# power.net
KiCad netlist of a schematic drawn in Altium Designer
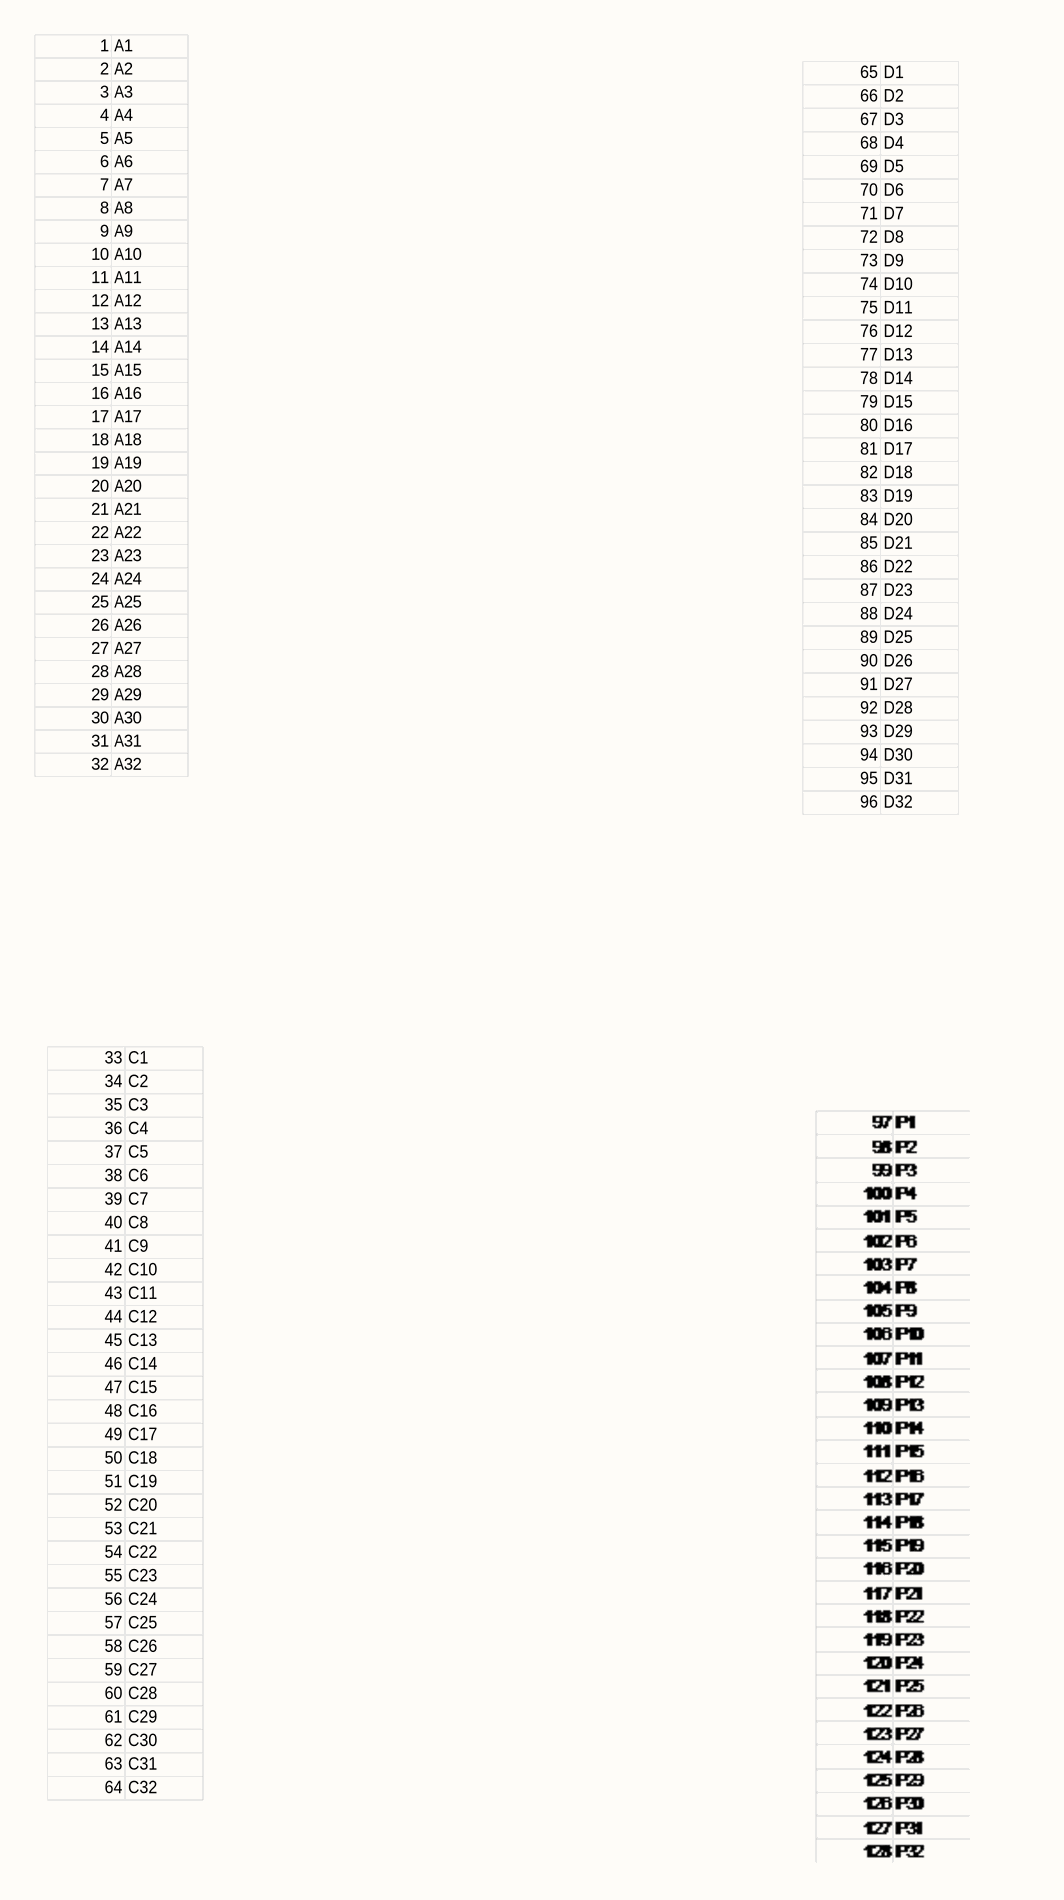
[diagram p0: power.SchDoc, left]
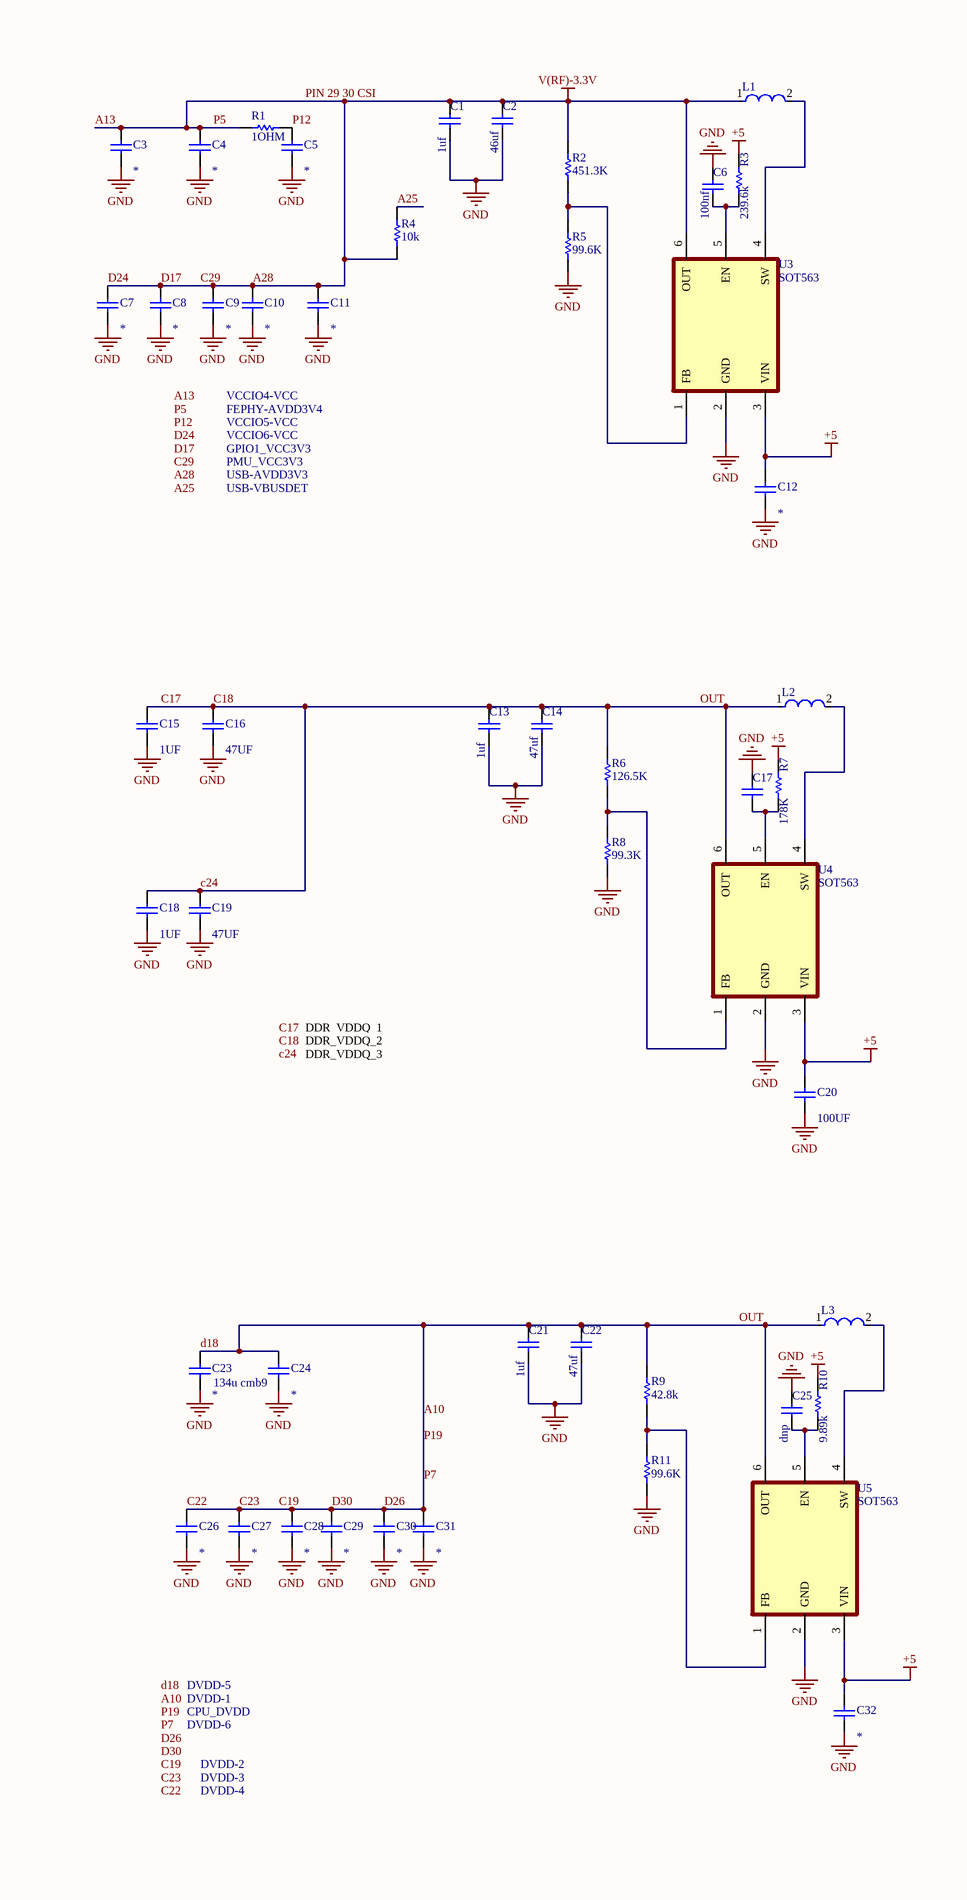
[diagram p1: power.SchDoc, right]

(export (version "E")
  (design (tool "Eeschema 10.0.6"))
  (components
    (comp (ref "C1")
      (value "1uf")
      (footprint "CAPC1005X56X25LL10T15")
      (libsource (lib "Altium Content Vault") (part "CAP"))
    )
    (comp (ref "C2")
      (value "46uf")
      (footprint "CAPC1005X56X25LL10T15")
      (libsource (lib "Altium Content Vault") (part "CAP"))
    )
    (comp (ref "C3")
      (value "*")
      (footprint "CAPC1005X56X25LL10T15")
      (libsource (lib "Altium Content Vault") (part "CAP"))
    )
    (comp (ref "C4")
      (value "*")
      (footprint "CAPC1005X56X25LL10T15")
      (libsource (lib "Altium Content Vault") (part "CAP"))
    )
    (comp (ref "C5")
      (value "*")
      (footprint "CAPC1005X56X25LL10T15")
      (libsource (lib "Altium Content Vault") (part "CAP"))
    )
    (comp (ref "C6")
      (value "100nf")
      (footprint "CAPC1005X56X25LL10T15")
      (libsource (lib "Altium Content Vault") (part "CAP"))
    )
    (comp (ref "C7")
      (value "*")
      (footprint "CAPC1005X56X25LL10T15")
      (libsource (lib "Altium Content Vault") (part "CAP"))
    )
    (comp (ref "C8")
      (value "*")
      (footprint "CAPC1005X56X25LL10T15")
      (libsource (lib "Altium Content Vault") (part "CAP"))
    )
    (comp (ref "C9")
      (value "*")
      (footprint "CAPC1005X56X25LL10T15")
      (libsource (lib "Altium Content Vault") (part "CAP"))
    )
    (comp (ref "C10")
      (value "*")
      (footprint "CAPC1005X56X25LL10T15")
      (libsource (lib "Altium Content Vault") (part "CAP"))
    )
    (comp (ref "C11")
      (value "*")
      (footprint "CAPC1005X56X25LL10T15")
      (libsource (lib "Altium Content Vault") (part "CAP"))
    )
    (comp (ref "C12")
      (value "*")
      (footprint "CAPC1005X56X25LL10T15")
      (libsource (lib "Altium Content Vault") (part "CAP"))
    )
    (comp (ref "C13")
      (value "1uf")
      (footprint "CAPC1005X56X25LL10T15")
      (libsource (lib "Altium Content Vault") (part "CAP"))
    )
    (comp (ref "C14")
      (value "47uf")
      (footprint "CAPC1005X56X25LL10T15")
      (libsource (lib "Altium Content Vault") (part "CAP"))
    )
    (comp (ref "C15")
      (value "1UF")
      (footprint "CAPC1005X56X25LL10T15")
      (libsource (lib "Altium Content Vault") (part "CAP"))
    )
    (comp (ref "C16")
      (value "47UF")
      (footprint "CAPC1005X56X25LL10T15")
      (libsource (lib "Altium Content Vault") (part "CAP"))
    )
    (comp (ref "C17")
      (value "~")
      (footprint "CAPC1005X56X25LL10T15")
      (libsource (lib "Altium Content Vault") (part "CAP"))
    )
    (comp (ref "C18")
      (value "1UF")
      (footprint "CAPC1005X56X25LL10T15")
      (libsource (lib "Altium Content Vault") (part "CAP"))
    )
    (comp (ref "C19")
      (value "47UF")
      (footprint "CAPC1005X56X25LL10T15")
      (libsource (lib "Altium Content Vault") (part "CAP"))
    )
    (comp (ref "C20")
      (value "100UF")
      (footprint "CAPC1005X56X25LL10T15")
      (libsource (lib "Altium Content Vault") (part "CAP"))
    )
    (comp (ref "C21")
      (value "1uf")
      (footprint "CAPC1005X56X25LL10T15")
      (libsource (lib "Altium Content Vault") (part "CAP"))
    )
    (comp (ref "C22")
      (value "47uf")
      (footprint "CAPC1005X56X25LL10T15")
      (libsource (lib "Altium Content Vault") (part "CAP"))
    )
    (comp (ref "C23")
      (value "*")
      (footprint "CAPC1005X56X25LL10T15")
      (libsource (lib "Altium Content Vault") (part "CAP"))
    )
    (comp (ref "C24")
      (value "*")
      (footprint "CAPC1005X56X25LL10T15")
      (libsource (lib "Altium Content Vault") (part "CAP"))
    )
    (comp (ref "C25")
      (value "dnp")
      (footprint "CAPC1005X56X25LL10T15")
      (libsource (lib "Altium Content Vault") (part "CAP"))
    )
    (comp (ref "C26")
      (value "*")
      (footprint "CAPC1005X56X25LL10T15")
      (libsource (lib "Altium Content Vault") (part "CAP"))
    )
    (comp (ref "C27")
      (value "*")
      (footprint "CAPC1005X56X25LL10T15")
      (libsource (lib "Altium Content Vault") (part "CAP"))
    )
    (comp (ref "C28")
      (value "*")
      (footprint "CAPC1005X56X25LL10T15")
      (libsource (lib "Altium Content Vault") (part "CAP"))
    )
    (comp (ref "C29")
      (value "*")
      (footprint "CAPC1005X56X25LL10T15")
      (libsource (lib "Altium Content Vault") (part "CAP"))
    )
    (comp (ref "C30")
      (value "*")
      (footprint "CAPC1005X56X25LL10T15")
      (libsource (lib "Altium Content Vault") (part "CAP"))
    )
    (comp (ref "C31")
      (value "*")
      (footprint "CAPC1005X56X25LL10T15")
      (libsource (lib "Altium Content Vault") (part "CAP"))
    )
    (comp (ref "C32")
      (value "*")
      (footprint "CAPC1005X56X25LL10T15")
      (libsource (lib "Altium Content Vault") (part "CAP"))
    )
    (comp (ref "L1")
      (value "~")
      (footprint "FP-LQH31CN_03-MFG")
      (libsource (lib "Altium Content Vault") (part "725321dda6339637d4d059423bc1c3c"))
    )
    (comp (ref "L2")
      (value "~")
      (footprint "FP-LQH31CN_03-MFG")
      (libsource (lib "Altium Content Vault") (part "725321dda6339637d4d059423bc1c3c"))
    )
    (comp (ref "L3")
      (value "~")
      (footprint "FP-LQH31CN_03-MFG")
      (libsource (lib "Altium Content Vault") (part "725321dda6339637d4d059423bc1c3c"))
    )
    (comp (ref "R1")
      (value "1OHM")
      (footprint "RESC1005X40X25LL05T10")
      (libsource (lib "Altium Content Vault") (part "RES"))
    )
    (comp (ref "R2")
      (value "451.3K")
      (footprint "RESC1005X40X25LL05T10")
      (libsource (lib "Altium Content Vault") (part "RES"))
    )
    (comp (ref "R3")
      (value "239.6k")
      (footprint "RESC1005X40X25LL05T10")
      (libsource (lib "Altium Content Vault") (part "RES"))
    )
    (comp (ref "R4")
      (value "10k")
      (footprint "RESC1005X40X25LL05T10")
      (libsource (lib "Altium Content Vault") (part "RES"))
    )
    (comp (ref "R5")
      (value "99.6K")
      (footprint "RESC1005X40X25LL05T10")
      (libsource (lib "Altium Content Vault") (part "RES"))
    )
    (comp (ref "R6")
      (value "126.5K")
      (footprint "RESC1005X40X25LL05T10")
      (libsource (lib "Altium Content Vault") (part "RES"))
    )
    (comp (ref "R7")
      (value "178K")
      (footprint "RESC1005X40X25LL05T10")
      (libsource (lib "Altium Content Vault") (part "RES"))
    )
    (comp (ref "R8")
      (value "99.3K")
      (footprint "RESC1005X40X25LL05T10")
      (libsource (lib "Altium Content Vault") (part "RES"))
    )
    (comp (ref "R9")
      (value "42.8k")
      (footprint "RESC1005X40X25LL05T10")
      (libsource (lib "Altium Content Vault") (part "RES"))
    )
    (comp (ref "R10")
      (value "9.89k")
      (footprint "RESC1005X40X25LL05T10")
      (libsource (lib "Altium Content Vault") (part "RES"))
    )
    (comp (ref "R11")
      (value "99.6K")
      (footprint "RESC1005X40X25LL05T10")
      (libsource (lib "Altium Content Vault") (part "RES"))
    )
    (comp (ref "U3") (value "SOT563") (libsource (lib "Schlib1") (part "SOT563")))
    (comp (ref "U4") (value "SOT563") (libsource (lib "Schlib1") (part "SOT563")))
    (comp (ref "U5") (value "SOT563") (libsource (lib "Schlib1") (part "SOT563")))
  )
  (nets
    (net (code "1") (name "+5") (class "Default")
      (node (ref "C12") (pin "2") (pinfunction "2_2") (pintype "passive"))
      (node (ref "C20") (pin "2") (pinfunction "2_2") (pintype "passive"))
      (node (ref "C32") (pin "2") (pinfunction "2_2") (pintype "passive"))
      (node (ref "R10") (pin "2") (pinfunction "2_2") (pintype "passive"))
      (node (ref "R3") (pin "2") (pinfunction "2_2") (pintype "passive"))
      (node (ref "R7") (pin "2") (pinfunction "2_2") (pintype "passive"))
      (node (ref "U3") (pin "3") (pinfunction "VIN_3") (pintype "open_collector"))
      (node (ref "U4") (pin "3") (pinfunction "VIN_3") (pintype "open_collector"))
      (node (ref "U5") (pin "3") (pinfunction "VIN_3") (pintype "open_collector"))
    )
    (net (code "2") (name "/A10") (class "Default")
      (node (ref "C13") (pin "2") (pinfunction "2_2") (pintype "passive"))
      (node (ref "C14") (pin "2") (pinfunction "2_2") (pintype "passive"))
      (node (ref "C15") (pin "2") (pinfunction "2_2") (pintype "passive"))
      (node (ref "C16") (pin "2") (pinfunction "2_2") (pintype "passive"))
      (node (ref "C18") (pin "2") (pinfunction "2_2") (pintype "passive"))
      (node (ref "C19") (pin "2") (pinfunction "2_2") (pintype "passive"))
      (node (ref "C21") (pin "2") (pinfunction "2_2") (pintype "passive"))
      (node (ref "C22") (pin "2") (pinfunction "2_2") (pintype "passive"))
      (node (ref "C23") (pin "2") (pinfunction "2_2") (pintype "passive"))
      (node (ref "C24") (pin "2") (pinfunction "2_2") (pintype "passive"))
      (node (ref "C26") (pin "2") (pinfunction "2_2") (pintype "passive"))
      (node (ref "C27") (pin "2") (pinfunction "2_2") (pintype "passive"))
      (node (ref "C28") (pin "2") (pinfunction "2_2") (pintype "passive"))
      (node (ref "C29") (pin "2") (pinfunction "2_2") (pintype "passive"))
      (node (ref "C30") (pin "2") (pinfunction "2_2") (pintype "passive"))
      (node (ref "C31") (pin "2") (pinfunction "2_2") (pintype "passive"))
      (node (ref "L2") (pin "1") (pinfunction "1_1") (pintype "passive"))
      (node (ref "L3") (pin "1") (pinfunction "1_1") (pintype "passive"))
      (node (ref "R6") (pin "2") (pinfunction "2_2") (pintype "passive"))
      (node (ref "R9") (pin "2") (pinfunction "2_2") (pintype "passive"))
      (node (ref "U4") (pin "6") (pinfunction "OUT_6") (pintype "open_collector"))
      (node (ref "U5") (pin "6") (pinfunction "OUT_6") (pintype "open_collector"))
    )
    (net (code "3") (name "/A25") (class "Default")
      (node (ref "R4") (pin "2") (pinfunction "2_2") (pintype "passive"))
    )
    (net (code "4") (name "/P12") (class "Default")
      (node (ref "C5") (pin "2") (pinfunction "2_2") (pintype "passive"))
      (node (ref "R1") (pin "1") (pinfunction "1_1") (pintype "passive"))
    )
    (net (code "5") (name "GND") (class "Default")
      (node (ref "C1") (pin "1") (pinfunction "1_1") (pintype "passive"))
      (node (ref "C10") (pin "1") (pinfunction "1_1") (pintype "passive"))
      (node (ref "C11") (pin "1") (pinfunction "1_1") (pintype "passive"))
      (node (ref "C12") (pin "1") (pinfunction "1_1") (pintype "passive"))
      (node (ref "C13") (pin "1") (pinfunction "1_1") (pintype "passive"))
      (node (ref "C14") (pin "1") (pinfunction "1_1") (pintype "passive"))
      (node (ref "C15") (pin "1") (pinfunction "1_1") (pintype "passive"))
      (node (ref "C16") (pin "1") (pinfunction "1_1") (pintype "passive"))
      (node (ref "C17") (pin "2") (pinfunction "2_2") (pintype "passive"))
      (node (ref "C18") (pin "1") (pinfunction "1_1") (pintype "passive"))
      (node (ref "C19") (pin "1") (pinfunction "1_1") (pintype "passive"))
      (node (ref "C2") (pin "1") (pinfunction "1_1") (pintype "passive"))
      (node (ref "C20") (pin "1") (pinfunction "1_1") (pintype "passive"))
      (node (ref "C21") (pin "1") (pinfunction "1_1") (pintype "passive"))
      (node (ref "C22") (pin "1") (pinfunction "1_1") (pintype "passive"))
      (node (ref "C23") (pin "1") (pinfunction "1_1") (pintype "passive"))
      (node (ref "C24") (pin "1") (pinfunction "1_1") (pintype "passive"))
      (node (ref "C25") (pin "2") (pinfunction "2_2") (pintype "passive"))
      (node (ref "C26") (pin "1") (pinfunction "1_1") (pintype "passive"))
      (node (ref "C27") (pin "1") (pinfunction "1_1") (pintype "passive"))
      (node (ref "C28") (pin "1") (pinfunction "1_1") (pintype "passive"))
      (node (ref "C29") (pin "1") (pinfunction "1_1") (pintype "passive"))
      (node (ref "C3") (pin "1") (pinfunction "1_1") (pintype "passive"))
      (node (ref "C30") (pin "1") (pinfunction "1_1") (pintype "passive"))
      (node (ref "C31") (pin "1") (pinfunction "1_1") (pintype "passive"))
      (node (ref "C32") (pin "1") (pinfunction "1_1") (pintype "passive"))
      (node (ref "C4") (pin "1") (pinfunction "1_1") (pintype "passive"))
      (node (ref "C5") (pin "1") (pinfunction "1_1") (pintype "passive"))
      (node (ref "C6") (pin "2") (pinfunction "2_2") (pintype "passive"))
      (node (ref "C7") (pin "1") (pinfunction "1_1") (pintype "passive"))
      (node (ref "C8") (pin "1") (pinfunction "1_1") (pintype "passive"))
      (node (ref "C9") (pin "1") (pinfunction "1_1") (pintype "passive"))
      (node (ref "R11") (pin "1") (pinfunction "1_1") (pintype "passive"))
      (node (ref "R5") (pin "1") (pinfunction "1_1") (pintype "passive"))
      (node (ref "R8") (pin "1") (pinfunction "1_1") (pintype "passive"))
      (node (ref "U3") (pin "2") (pinfunction "GND_2") (pintype "power_in"))
      (node (ref "U4") (pin "2") (pinfunction "GND_2") (pintype "power_in"))
      (node (ref "U5") (pin "2") (pinfunction "GND_2") (pintype "power_in"))
    )
    (net (code "6") (name "Net-(U3-EN)") (class "Default")
      (node (ref "C6") (pin "1") (pinfunction "1_1") (pintype "passive"))
      (node (ref "R3") (pin "1") (pinfunction "1_1") (pintype "passive"))
      (node (ref "U3") (pin "5") (pinfunction "EN_5") (pintype "open_collector"))
    )
    (net (code "7") (name "Net-(U3-FB)") (class "Default")
      (node (ref "R2") (pin "1") (pinfunction "1_1") (pintype "passive"))
      (node (ref "R5") (pin "2") (pinfunction "2_2") (pintype "passive"))
      (node (ref "U3") (pin "1") (pinfunction "FB_1") (pintype "open_collector"))
    )
    (net (code "8") (name "Net-(U3-SW)") (class "Default")
      (node (ref "L1") (pin "2") (pinfunction "2_2") (pintype "passive"))
      (node (ref "U3") (pin "4") (pinfunction "SW_4") (pintype "open_collector"))
    )
    (net (code "9") (name "Net-(U4-EN)") (class "Default")
      (node (ref "C17") (pin "1") (pinfunction "1_1") (pintype "passive"))
      (node (ref "R7") (pin "1") (pinfunction "1_1") (pintype "passive"))
      (node (ref "U4") (pin "5") (pinfunction "EN_5") (pintype "open_collector"))
    )
    (net (code "10") (name "Net-(U4-FB)") (class "Default")
      (node (ref "R6") (pin "1") (pinfunction "1_1") (pintype "passive"))
      (node (ref "R8") (pin "2") (pinfunction "2_2") (pintype "passive"))
      (node (ref "U4") (pin "1") (pinfunction "FB_1") (pintype "open_collector"))
    )
    (net (code "11") (name "Net-(U4-SW)") (class "Default")
      (node (ref "L2") (pin "2") (pinfunction "2_2") (pintype "passive"))
      (node (ref "U4") (pin "4") (pinfunction "SW_4") (pintype "open_collector"))
    )
    (net (code "12") (name "Net-(U5-EN)") (class "Default")
      (node (ref "C25") (pin "1") (pinfunction "1_1") (pintype "passive"))
      (node (ref "R10") (pin "1") (pinfunction "1_1") (pintype "passive"))
      (node (ref "U5") (pin "5") (pinfunction "EN_5") (pintype "open_collector"))
    )
    (net (code "13") (name "Net-(U5-FB)") (class "Default")
      (node (ref "R11") (pin "2") (pinfunction "2_2") (pintype "passive"))
      (node (ref "R9") (pin "1") (pinfunction "1_1") (pintype "passive"))
      (node (ref "U5") (pin "1") (pinfunction "FB_1") (pintype "open_collector"))
    )
    (net (code "14") (name "Net-(U5-SW)") (class "Default")
      (node (ref "L3") (pin "2") (pinfunction "2_2") (pintype "passive"))
      (node (ref "U5") (pin "4") (pinfunction "SW_4") (pintype "open_collector"))
    )
    (net (code "15") (name "V(RF)-3.3V") (class "Default")
      (node (ref "C1") (pin "2") (pinfunction "2_2") (pintype "passive"))
      (node (ref "C10") (pin "2") (pinfunction "2_2") (pintype "passive"))
      (node (ref "C11") (pin "2") (pinfunction "2_2") (pintype "passive"))
      (node (ref "C2") (pin "2") (pinfunction "2_2") (pintype "passive"))
      (node (ref "C3") (pin "2") (pinfunction "2_2") (pintype "passive"))
      (node (ref "C4") (pin "2") (pinfunction "2_2") (pintype "passive"))
      (node (ref "C7") (pin "2") (pinfunction "2_2") (pintype "passive"))
      (node (ref "C8") (pin "2") (pinfunction "2_2") (pintype "passive"))
      (node (ref "C9") (pin "2") (pinfunction "2_2") (pintype "passive"))
      (node (ref "L1") (pin "1") (pinfunction "1_1") (pintype "passive"))
      (node (ref "R1") (pin "2") (pinfunction "2_2") (pintype "passive"))
      (node (ref "R2") (pin "2") (pinfunction "2_2") (pintype "passive"))
      (node (ref "R4") (pin "1") (pinfunction "1_1") (pintype "passive"))
      (node (ref "U3") (pin "6") (pinfunction "OUT_6") (pintype "open_collector"))
    )
  )
)
